# sensor_board_v0_6.net
KiCad netlist of a schematic drawn in EAGLE
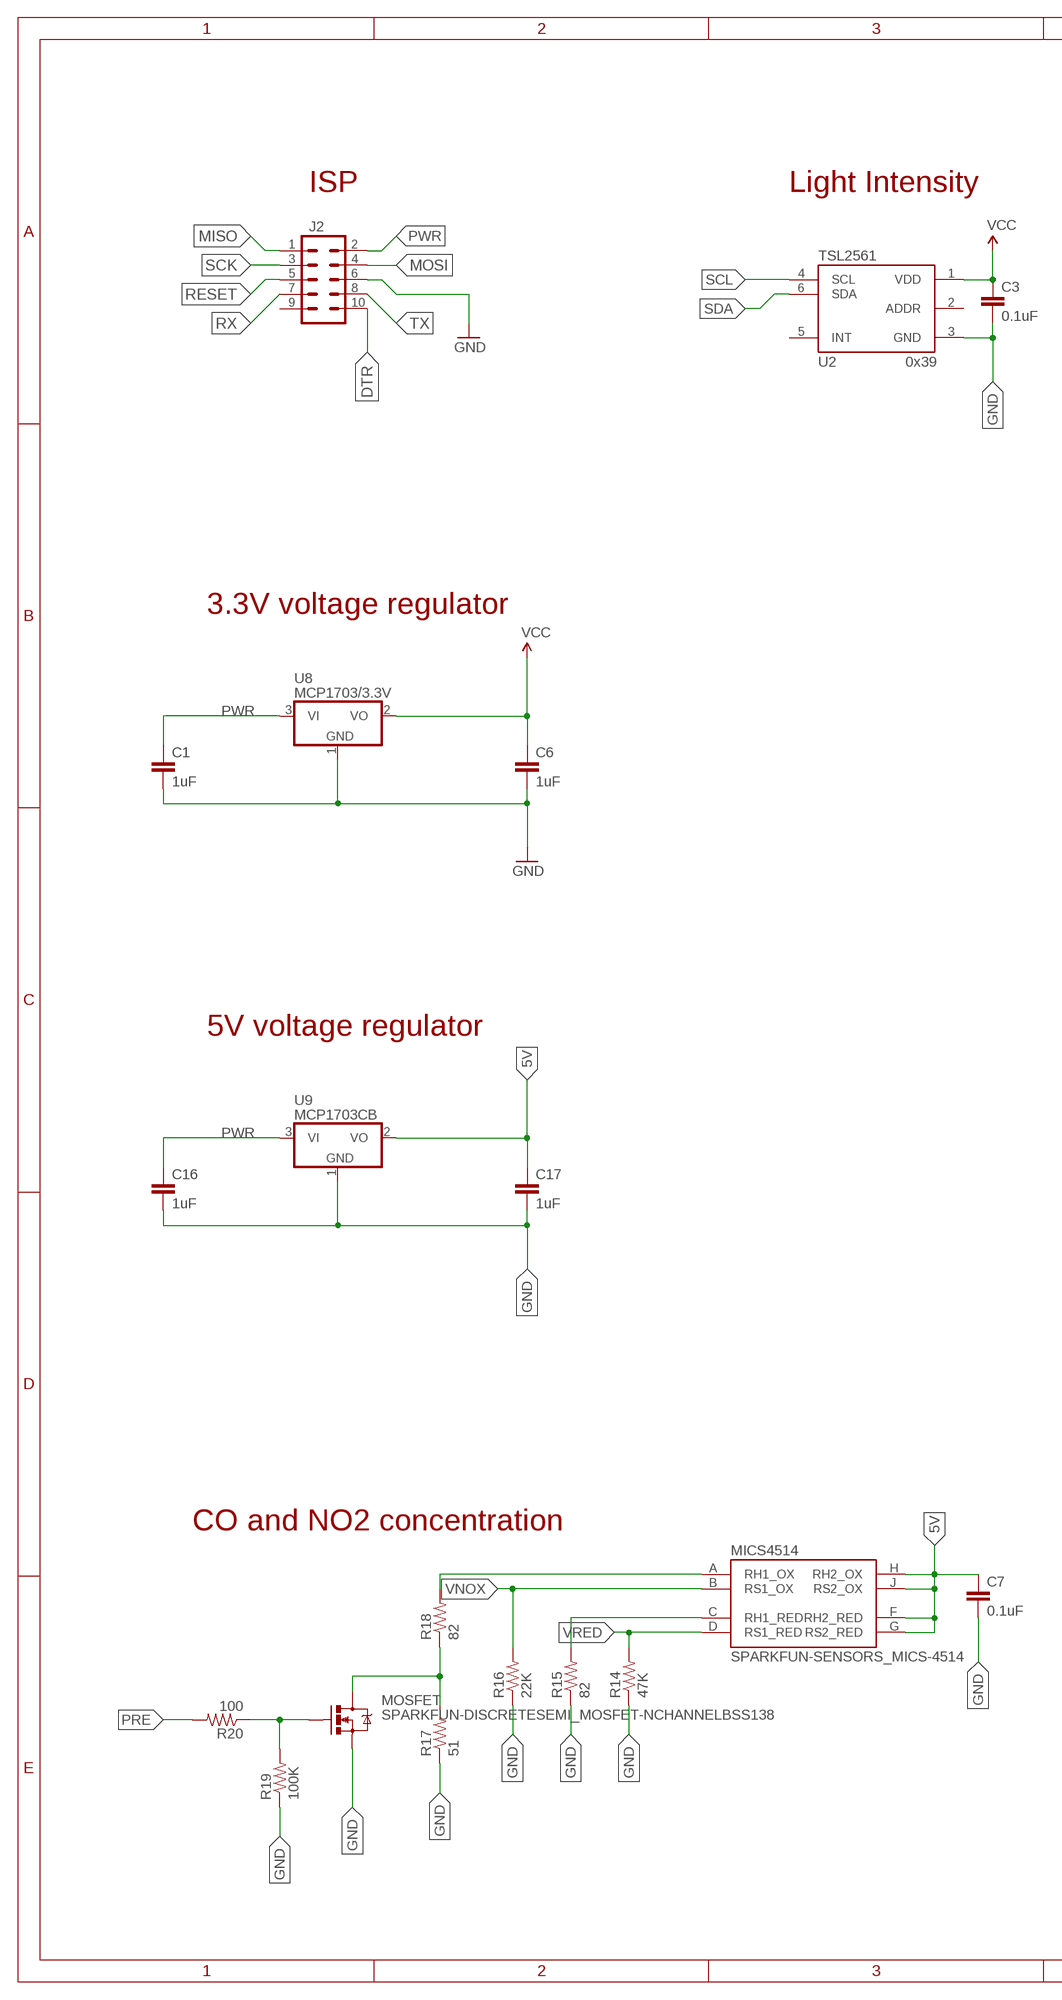
[diagram p0: schematic, sheet 1, part 1 of 2]
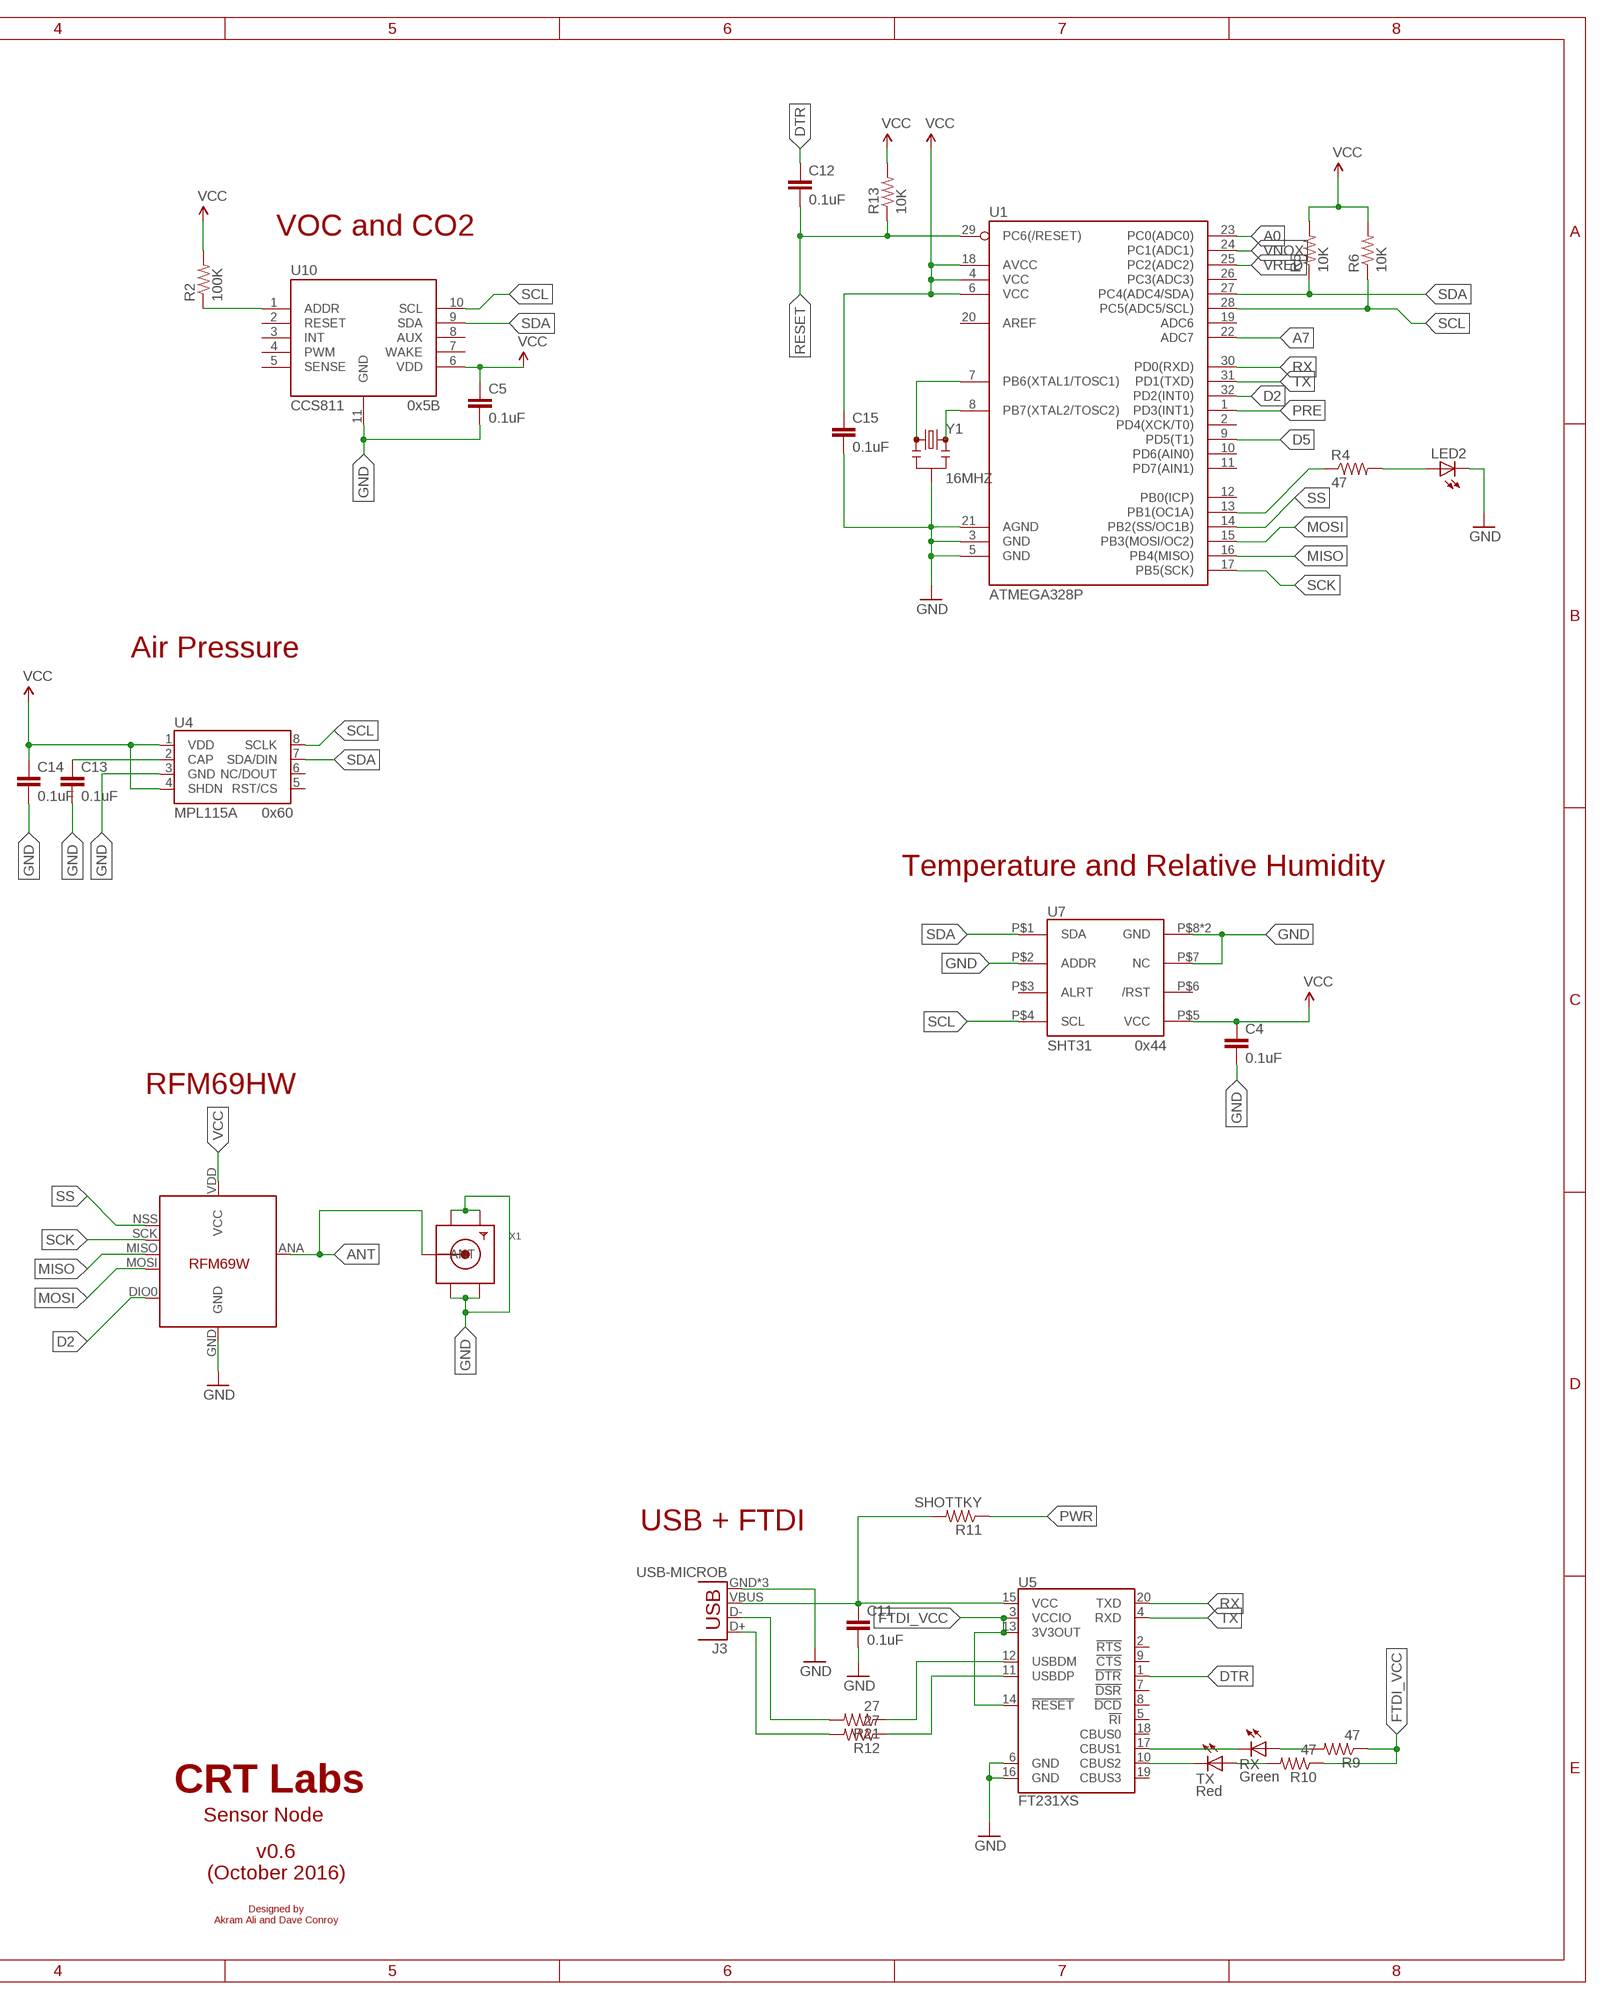
[diagram p1: schematic, sheet 1, part 2 of 2]

(export (version "E")
  (design (tool "Eeschema 10.0.6"))
  (components
    (comp (ref "C1")
      (value "1uF")
      (footprint "eagle-import:0805")
      (libsource (lib "eagle-import") (part "CAP0805"))
    )
    (comp (ref "C3")
      (value "0.1uF")
      (footprint "eagle-import:0805")
      (libsource (lib "eagle-import") (part "SparkFun-Passives_CAP0805"))
    )
    (comp (ref "C4")
      (value "0.1uF")
      (footprint "eagle-import:0805")
      (libsource (lib "eagle-import") (part "SparkFun-Passives_CAP0805"))
    )
    (comp (ref "C5")
      (value "0.1uF")
      (footprint "eagle-import:0805")
      (libsource (lib "eagle-import") (part "SparkFun-Passives_CAP0805"))
    )
    (comp (ref "C6")
      (value "1uF")
      (footprint "eagle-import:0805")
      (libsource (lib "eagle-import") (part "CAP0805"))
    )
    (comp (ref "C7")
      (value "0.1uF")
      (footprint "eagle-import:0805")
      (libsource (lib "eagle-import") (part "SparkFun-Passives_CAP0805"))
    )
    (comp (ref "C11")
      (value "0.1uF")
      (footprint "eagle-import:0805")
      (libsource (lib "eagle-import") (part "CAP0805"))
    )
    (comp (ref "C12")
      (value "0.1uF")
      (footprint "eagle-import:0805")
      (libsource (lib "eagle-import") (part "SparkFun-Passives_CAP0805"))
    )
    (comp (ref "C13")
      (value "0.1uF")
      (footprint "eagle-import:0805")
      (libsource (lib "eagle-import") (part "SparkFun-Passives_CAP0805"))
    )
    (comp (ref "C14")
      (value "0.1uF")
      (footprint "eagle-import:0805")
      (libsource (lib "eagle-import") (part "SparkFun-Passives_CAP0805"))
    )
    (comp (ref "C15")
      (value "0.1uF")
      (footprint "eagle-import:0805")
      (libsource (lib "eagle-import") (part "SparkFun-Passives_CAP0805"))
    )
    (comp (ref "C16")
      (value "1uF")
      (footprint "eagle-import:0805")
      (libsource (lib "eagle-import") (part "CAP0805"))
    )
    (comp (ref "C17")
      (value "1uF")
      (footprint "eagle-import:0805")
      (libsource (lib "eagle-import") (part "CAP0805"))
    )
    (comp (ref "J2")
      (value "M05X2PTH")
      (footprint "eagle-import:AVR_ICSP")
      (libsource (lib "eagle-import") (part "M05X2PTH"))
    )
    (comp (ref "J3")
      (value "USB-MICROB")
      (footprint "eagle-import:USB-MICROB")
      (libsource (lib "eagle-import") (part "USB-MICROB"))
    )
    (comp (ref "LED2")
      (value "LEDCHIPLED_0805")
      (footprint "eagle-import:CHIPLED_0805")
      (libsource (lib "eagle-import") (part "LEDCHIPLED_0805"))
    )
    (comp (ref "MICS4514")
      (value "SPARKFUN-SENSORS_MICS-4514")
      (footprint "eagle-import:SPARKFUN-SENSORS_MICS_10-SMD")
      (libsource (lib "eagle-import") (part "SPARKFUN-SENSORS_MICS-4514"))
    )
    (comp (ref "MOSFET")
      (value "SPARKFUN-DISCRETESEMI_MOSFET-NCHANNELBSS138")
      (footprint "eagle-import:SPARKFUN-DISCRETESEMI_SOT23-3")
      (libsource (lib "eagle-import") (part "SPARKFUN-DISCRETESEMI_MOSFET-NCHANNELBSS138"))
    )
    (comp (ref "R2")
      (value "100K")
      (footprint "eagle-import:0805")
      (libsource (lib "eagle-import") (part "RESISTOR0805-RES"))
    )
    (comp (ref "R4")
      (value "47")
      (footprint "eagle-import:0805")
      (libsource (lib "eagle-import") (part "SparkFun-Resistors_RESISTOR0805-RES"))
    )
    (comp (ref "R5")
      (value "10K")
      (footprint "eagle-import:0805")
      (libsource (lib "eagle-import") (part "SparkFun-Resistors_RESISTOR0805-RES"))
    )
    (comp (ref "R6")
      (value "10K")
      (footprint "eagle-import:0805")
      (libsource (lib "eagle-import") (part "SparkFun-Resistors_RESISTOR0805-RES"))
    )
    (comp (ref "R9")
      (value "47")
      (footprint "eagle-import:0805")
      (libsource (lib "eagle-import") (part "RESISTOR0805-RES"))
    )
    (comp (ref "R10")
      (value "47")
      (footprint "eagle-import:0805")
      (libsource (lib "eagle-import") (part "RESISTOR0805-RES"))
    )
    (comp (ref "R11")
      (value "SHOTTKY")
      (footprint "eagle-import:0805")
      (libsource (lib "eagle-import") (part "RESISTOR0805-RES"))
    )
    (comp (ref "R12")
      (value "27")
      (footprint "eagle-import:0805")
      (libsource (lib "eagle-import") (part "RESISTOR0805-RES"))
    )
    (comp (ref "R13")
      (value "10K")
      (footprint "eagle-import:0805")
      (libsource (lib "eagle-import") (part "RESISTOR0805-RES"))
    )
    (comp (ref "R14")
      (value "47K")
      (footprint "eagle-import:0805")
      (libsource (lib "eagle-import") (part "RESISTOR0805-RES"))
    )
    (comp (ref "R15")
      (value "82")
      (footprint "eagle-import:0805")
      (libsource (lib "eagle-import") (part "RESISTOR0805-RES"))
    )
    (comp (ref "R16")
      (value "22K")
      (footprint "eagle-import:0805")
      (libsource (lib "eagle-import") (part "RESISTOR0805-RES"))
    )
    (comp (ref "R17")
      (value "51")
      (footprint "eagle-import:0805")
      (libsource (lib "eagle-import") (part "RESISTOR0805-RES"))
    )
    (comp (ref "R18")
      (value "82")
      (footprint "eagle-import:0805")
      (libsource (lib "eagle-import") (part "RESISTOR0805-RES"))
    )
    (comp (ref "R19")
      (value "100K")
      (footprint "eagle-import:0805")
      (libsource (lib "eagle-import") (part "RESISTOR0805-RES"))
    )
    (comp (ref "R20")
      (value "100")
      (footprint "eagle-import:0805")
      (libsource (lib "eagle-import") (part "RESISTOR0805-RES"))
    )
    (comp (ref "R21")
      (value "27")
      (footprint "eagle-import:0805")
      (libsource (lib "eagle-import") (part "RESISTOR0805-RES"))
    )
    (comp (ref "RX")
      (value "Green")
      (footprint "eagle-import:CHIPLED_0805")
      (libsource (lib "eagle-import") (part "LEDCHIPLED_0805"))
    )
    (comp (ref "TX")
      (value "Red")
      (footprint "eagle-import:CHIPLED_0805")
      (libsource (lib "eagle-import") (part "LEDCHIPLED_0805"))
    )
    (comp (ref "U1")
      (value "ATMEGA328P")
      (footprint "eagle-import:TQFP32-08")
      (fields (field (name "MPN") "ATMEGA328PB-AU"))
      (libsource (lib "eagle-import") (part "ATMEGA328P_TQFP"))
    )
    (comp (ref "U2")
      (value "TSL2561")
      (footprint "eagle-import:FN-6")
      (fields (field (name "MANF") "AMS-TAOS-USA-Inc.") (field (name "MPN") "TSL2561FN"))
      (libsource (lib "eagle-import") (part "TSL2561FN"))
    )
    (comp (ref "U4")
      (value "MPL115A")
      (footprint "eagle-import:LGA8")
      (libsource (lib "eagle-import") (part "MPL115A"))
    )
    (comp (ref "U5")
      (value "FT231XS")
      (footprint "eagle-import:SSOP20_L")
      (libsource (lib "eagle-import") (part "FT231XS"))
    )
    (comp (ref "U7")
      (value "SHT31")
      (footprint "eagle-import:SHT3X")
      (fields (field (name "MPN") "SHT31-DIS-B"))
      (libsource (lib "eagle-import") (part "SHT31-DIS"))
    )
    (comp (ref "U8")
      (value "MCP1703/3.3V")
      (footprint "eagle-import:SOT23")
      (fields (field (name "MPN") "MCP1703T-2502E/CB"))
      (libsource (lib "eagle-import") (part "MCP1703CB"))
    )
    (comp (ref "U9")
      (value "MCP1703CB")
      (footprint "eagle-import:SOT23")
      (fields (field (name "MPN") "MCP1703T-2502E/CB"))
      (libsource (lib "eagle-import") (part "MCP1703CB"))
    )
    (comp (ref "U10")
      (value "CCS811")
      (footprint "eagle-import:LGA")
      (libsource (lib "eagle-import") (part "CCS811-I2C"))
    )
    (comp (ref "U11")
      (value "RFM69HW")
      (footprint "eagle-import:LOWPOWERLAB_RFM69W-MINPADS")
      (libsource (lib "eagle-import") (part "LOWPOWERLAB_RFM69"))
    )
    (comp (ref "X1")
      (value "SMACONNECTOR_EDGE")
      (footprint "eagle-import:SMA_EDGELAUNCH")
      (libsource (lib "eagle-import") (part "SMACONNECTOR_EDGE"))
    )
    (comp (ref "Y1")
      (value "16MHZ")
      (footprint "eagle-import:RESONATOR-SMD")
      (libsource (lib "eagle-import") (part "RESONATOR16MHZ"))
    )
  )
  (nets
    (net (code "1") (name "5V") (class "Default")
      (node (ref "C17") (pin "1") (pinfunction "1_1") (pintype "passive"))
      (node (ref "C7") (pin "1") (pinfunction "1_1") (pintype "passive"))
      (node (ref "MICS4514") (pin "F") (pinfunction "RH2_RED_F") (pintype "bidirectional"))
      (node (ref "MICS4514") (pin "G") (pinfunction "RS2_RED_G") (pintype "bidirectional"))
      (node (ref "MICS4514") (pin "H") (pinfunction "RH2_OX_H") (pintype "bidirectional"))
      (node (ref "MICS4514") (pin "J") (pinfunction "RS2_OX_J") (pintype "bidirectional"))
      (node (ref "U9") (pin "2") (pinfunction "VO_2") (pintype "passive"))
    )
    (net (code "2") (name "A0") (class "Default")
      (node (ref "U1") (pin "23") (pinfunction "PC0(ADC0)_23") (pintype "bidirectional"))
    )
    (net (code "3") (name "A7") (class "Default")
      (node (ref "U1") (pin "22") (pinfunction "ADC7_22") (pintype "bidirectional"))
    )
    (net (code "4") (name "ANT") (class "Default")
      (node (ref "U11") (pin "ANA") (pinfunction "ANT_ANA") (pintype "passive"))
      (node (ref "X1") (pin "P") (pinfunction "ANT_P") (pintype "bidirectional"))
    )
    (net (code "5") (name "D2") (class "Default")
      (node (ref "U1") (pin "32") (pinfunction "PD2(INT0)_32") (pintype "bidirectional"))
      (node (ref "U11") (pin "DIO0") (pinfunction "DIO0_DIO0") (pintype "open_collector"))
    )
    (net (code "6") (name "D5") (class "Default")
      (node (ref "U1") (pin "9") (pinfunction "PD5(T1)_9") (pintype "bidirectional"))
    )
    (net (code "7") (name "DTR") (class "Default")
      (node (ref "C12") (pin "1") (pinfunction "1_1") (pintype "passive"))
      (node (ref "J2") (pin "10") (pinfunction "10_10") (pintype "passive"))
      (node (ref "U5") (pin "1") (pinfunction "~{DTR}_1") (pintype "bidirectional"))
    )
    (net (code "8") (name "FTDI_VCC") (class "Default")
      (node (ref "R10") (pin "1") (pinfunction "1_1") (pintype "passive"))
      (node (ref "R9") (pin "1") (pinfunction "1_1") (pintype "passive"))
      (node (ref "U5") (pin "13") (pinfunction "3V3OUT_13") (pintype "bidirectional"))
      (node (ref "U5") (pin "14") (pinfunction "~{RESET}_14") (pintype "bidirectional"))
      (node (ref "U5") (pin "3") (pinfunction "VCCIO_3") (pintype "bidirectional"))
    )
    (net (code "9") (name "GND") (class "Default")
      (node (ref "C1") (pin "2") (pinfunction "2_2") (pintype "passive"))
      (node (ref "C11") (pin "2") (pinfunction "2_2") (pintype "passive"))
      (node (ref "C13") (pin "2") (pinfunction "2_2") (pintype "passive"))
      (node (ref "C14") (pin "2") (pinfunction "2_2") (pintype "passive"))
      (node (ref "C15") (pin "2") (pinfunction "2_2") (pintype "passive"))
      (node (ref "C16") (pin "2") (pinfunction "2_2") (pintype "passive"))
      (node (ref "C17") (pin "2") (pinfunction "2_2") (pintype "passive"))
      (node (ref "C3") (pin "2") (pinfunction "2_2") (pintype "passive"))
      (node (ref "C4") (pin "2") (pinfunction "2_2") (pintype "passive"))
      (node (ref "C5") (pin "2") (pinfunction "2_2") (pintype "passive"))
      (node (ref "C6") (pin "2") (pinfunction "2_2") (pintype "passive"))
      (node (ref "C7") (pin "2") (pinfunction "2_2") (pintype "passive"))
      (node (ref "J2") (pin "6") (pinfunction "6_6") (pintype "passive"))
      (node (ref "J3") (pin "GND") (pinfunction "GND_GND") (pintype "bidirectional"))
      (node (ref "J3") (pin "MT1") (pinfunction "GND_MT1") (pintype "bidirectional"))
      (node (ref "J3") (pin "MT2") (pinfunction "GND_MT2") (pintype "bidirectional"))
      (node (ref "LED2") (pin "C") (pinfunction "C_C") (pintype "passive"))
      (node (ref "MOSFET") (pin "2") (pinfunction "S_2") (pintype "passive"))
      (node (ref "R14") (pin "1") (pinfunction "1_1") (pintype "passive"))
      (node (ref "R15") (pin "1") (pinfunction "1_1") (pintype "passive"))
      (node (ref "R16") (pin "1") (pinfunction "1_1") (pintype "passive"))
      (node (ref "R17") (pin "1") (pinfunction "1_1") (pintype "passive"))
      (node (ref "R19") (pin "1") (pinfunction "1_1") (pintype "passive"))
      (node (ref "U1") (pin "21") (pinfunction "AGND_21") (pintype "bidirectional"))
      (node (ref "U1") (pin "3") (pinfunction "GND_3") (pintype "bidirectional"))
      (node (ref "U1") (pin "5") (pinfunction "GND_5") (pintype "bidirectional"))
      (node (ref "U10") (pin "11") (pinfunction "GND_11") (pintype "bidirectional"))
      (node (ref "U11") (pin "GND") (pinfunction "GND_GND") (pintype "power_in"))
      (node (ref "U2") (pin "3") (pinfunction "GND_3") (pintype "power_in"))
      (node (ref "U4") (pin "3") (pinfunction "GND_3") (pintype "bidirectional"))
      (node (ref "U5") (pin "16") (pinfunction "GND_16") (pintype "bidirectional"))
      (node (ref "U5") (pin "6") (pinfunction "GND_6") (pintype "bidirectional"))
      (node (ref "U7") (pin "P$2") (pinfunction "ADDR_P$2") (pintype "bidirectional"))
      (node (ref "U7") (pin "P$7") (pinfunction "NC_P$7") (pintype "bidirectional"))
      (node (ref "U7") (pin "P$8") (pinfunction "GND_P$8") (pintype "bidirectional"))
      (node (ref "U7") (pin "PAD") (pinfunction "GND_PAD") (pintype "bidirectional"))
      (node (ref "U8") (pin "1") (pinfunction "GND_1") (pintype "passive"))
      (node (ref "U9") (pin "1") (pinfunction "GND_1") (pintype "passive"))
      (node (ref "X1") (pin "GND@1") (pinfunction "GND4_GND@1") (pintype "power_in"))
      (node (ref "X1") (pin "GND@2") (pinfunction "GND3_GND@2") (pintype "power_in"))
      (node (ref "X1") (pin "GND@3") (pinfunction "GND2_GND@3") (pintype "power_in"))
      (node (ref "X1") (pin "GND@4") (pinfunction "GND1_GND@4") (pintype "power_in"))
      (node (ref "Y1") (pin "2") (pinfunction "2_2") (pintype "passive"))
    )
    (net (code "10") (name "MISO") (class "Default")
      (node (ref "J2") (pin "1") (pinfunction "1_1") (pintype "passive"))
      (node (ref "U1") (pin "16") (pinfunction "PB4(MISO)_16") (pintype "bidirectional"))
      (node (ref "U11") (pin "MISO") (pinfunction "MISO_MISO") (pintype "input"))
    )
    (net (code "11") (name "MOSI") (class "Default")
      (node (ref "J2") (pin "4") (pinfunction "4_4") (pintype "passive"))
      (node (ref "U1") (pin "15") (pinfunction "PB3(MOSI/OC2)_15") (pintype "bidirectional"))
      (node (ref "U11") (pin "MOSI") (pinfunction "MOSI_MOSI") (pintype "output"))
    )
    (net (code "12") (name "Net-(J3-PadD+)") (class "Default")
      (node (ref "J3") (pin "D+") (pinfunction "D+_D+") (pintype "bidirectional"))
      (node (ref "R12") (pin "2") (pinfunction "2_2") (pintype "passive"))
    )
    (net (code "13") (name "Net-(J3-PadD-)") (class "Default")
      (node (ref "J3") (pin "D-") (pinfunction "D-_D-") (pintype "bidirectional"))
      (node (ref "R21") (pin "2") (pinfunction "2_2") (pintype "passive"))
    )
    (net (code "14") (name "Net-(LED2-PadA)") (class "Default")
      (node (ref "LED2") (pin "A") (pinfunction "A_A") (pintype "passive"))
      (node (ref "R4") (pin "2") (pinfunction "2_2") (pintype "passive"))
    )
    (net (code "15") (name "Net-(MICS4514-RH1_OX)") (class "Default")
      (node (ref "MICS4514") (pin "A") (pinfunction "RH1_OX_A") (pintype "bidirectional"))
      (node (ref "R18") (pin "2") (pinfunction "2_2") (pintype "passive"))
    )
    (net (code "16") (name "Net-(MICS4514-RH1_RED)") (class "Default")
      (node (ref "MICS4514") (pin "C") (pinfunction "RH1_RED_C") (pintype "bidirectional"))
      (node (ref "R15") (pin "2") (pinfunction "2_2") (pintype "passive"))
    )
    (net (code "17") (name "Net-(MOSFET-D)") (class "Default")
      (node (ref "MOSFET") (pin "3") (pinfunction "D_3") (pintype "passive"))
      (node (ref "R17") (pin "2") (pinfunction "2_2") (pintype "passive"))
      (node (ref "R18") (pin "1") (pinfunction "1_1") (pintype "passive"))
    )
    (net (code "18") (name "Net-(MOSFET-G)") (class "Default")
      (node (ref "MOSFET") (pin "1") (pinfunction "G_1") (pintype "passive"))
      (node (ref "R19") (pin "2") (pinfunction "2_2") (pintype "passive"))
      (node (ref "R20") (pin "1") (pinfunction "1_1") (pintype "passive"))
    )
    (net (code "19") (name "Net-(R9-Pad2)") (class "Default")
      (node (ref "R9") (pin "2") (pinfunction "2_2") (pintype "passive"))
      (node (ref "RX") (pin "A") (pinfunction "A_A") (pintype "passive"))
    )
    (net (code "20") (name "Net-(R10-Pad2)") (class "Default")
      (node (ref "R10") (pin "2") (pinfunction "2_2") (pintype "passive"))
      (node (ref "TX") (pin "A") (pinfunction "A_A") (pintype "passive"))
    )
    (net (code "21") (name "Net-(U1-PB1(OC1A))") (class "Default")
      (node (ref "R4") (pin "1") (pinfunction "1_1") (pintype "passive"))
      (node (ref "U1") (pin "13") (pinfunction "PB1(OC1A)_13") (pintype "bidirectional"))
    )
    (net (code "22") (name "Net-(U1-PB6(XTAL1{slash}TOSC1))") (class "Default")
      (node (ref "U1") (pin "7") (pinfunction "PB6(XTAL1/TOSC1)_7") (pintype "bidirectional"))
      (node (ref "Y1") (pin "1") (pinfunction "1_1") (pintype "passive"))
    )
    (net (code "23") (name "Net-(U1-PB7(XTAL2{slash}TOSC2))") (class "Default")
      (node (ref "U1") (pin "8") (pinfunction "PB7(XTAL2/TOSC2)_8") (pintype "bidirectional"))
      (node (ref "Y1") (pin "3") (pinfunction "3_3") (pintype "passive"))
    )
    (net (code "24") (name "Net-(U4-CAP)") (class "Default")
      (node (ref "C13") (pin "1") (pinfunction "1_1") (pintype "passive"))
      (node (ref "U4") (pin "2") (pinfunction "CAP_2") (pintype "bidirectional"))
    )
    (net (code "25") (name "Net-(U5-CBUS1)") (class "Default")
      (node (ref "RX") (pin "C") (pinfunction "C_C") (pintype "passive"))
      (node (ref "U5") (pin "17") (pinfunction "CBUS1_17") (pintype "bidirectional"))
    )
    (net (code "26") (name "Net-(U5-CBUS2)") (class "Default")
      (node (ref "TX") (pin "C") (pinfunction "C_C") (pintype "passive"))
      (node (ref "U5") (pin "10") (pinfunction "CBUS2_10") (pintype "bidirectional"))
    )
    (net (code "27") (name "Net-(U5-USBDM)") (class "Default")
      (node (ref "R21") (pin "1") (pinfunction "1_1") (pintype "passive"))
      (node (ref "U5") (pin "12") (pinfunction "USBDM_12") (pintype "bidirectional"))
    )
    (net (code "28") (name "Net-(U5-USBDP)") (class "Default")
      (node (ref "R12") (pin "1") (pinfunction "1_1") (pintype "passive"))
      (node (ref "U5") (pin "11") (pinfunction "USBDP_11") (pintype "bidirectional"))
    )
    (net (code "29") (name "Net-(U5-VCC)") (class "Default")
      (node (ref "C11") (pin "1") (pinfunction "1_1") (pintype "passive"))
      (node (ref "J3") (pin "VBUS") (pinfunction "VBUS_VBUS") (pintype "bidirectional"))
      (node (ref "R11") (pin "2") (pinfunction "2_2") (pintype "passive"))
      (node (ref "U5") (pin "15") (pinfunction "VCC_15") (pintype "bidirectional"))
    )
    (net (code "30") (name "Net-(U10-ADDR)") (class "Default")
      (node (ref "R2") (pin "1") (pinfunction "1_1") (pintype "passive"))
      (node (ref "U10") (pin "1") (pinfunction "ADDR_1") (pintype "bidirectional"))
    )
    (net (code "31") (name "PRE") (class "Default")
      (node (ref "R20") (pin "2") (pinfunction "2_2") (pintype "passive"))
      (node (ref "U1") (pin "1") (pinfunction "PD3(INT1)_1") (pintype "bidirectional"))
    )
    (net (code "32") (name "PWR") (class "Default")
      (node (ref "C1") (pin "1") (pinfunction "1_1") (pintype "passive"))
      (node (ref "C16") (pin "1") (pinfunction "1_1") (pintype "passive"))
      (node (ref "J2") (pin "2") (pinfunction "2_2") (pintype "passive"))
      (node (ref "R11") (pin "1") (pinfunction "1_1") (pintype "passive"))
      (node (ref "U8") (pin "3") (pinfunction "VI_3") (pintype "input"))
      (node (ref "U9") (pin "3") (pinfunction "VI_3") (pintype "input"))
    )
    (net (code "33") (name "RESET") (class "Default")
      (node (ref "C12") (pin "2") (pinfunction "2_2") (pintype "passive"))
      (node (ref "J2") (pin "5") (pinfunction "5_5") (pintype "passive"))
      (node (ref "R13") (pin "1") (pinfunction "1_1") (pintype "passive"))
      (node (ref "U1") (pin "29") (pinfunction "PC6(/RESET)_29") (pintype "bidirectional"))
    )
    (net (code "34") (name "RX") (class "Default")
      (node (ref "J2") (pin "7") (pinfunction "7_7") (pintype "passive"))
      (node (ref "U1") (pin "30") (pinfunction "PD0(RXD)_30") (pintype "bidirectional"))
      (node (ref "U5") (pin "20") (pinfunction "TXD_20") (pintype "bidirectional"))
    )
    (net (code "35") (name "SCK") (class "Default")
      (node (ref "J2") (pin "3") (pinfunction "3_3") (pintype "passive"))
      (node (ref "U1") (pin "17") (pinfunction "PB5(SCK)_17") (pintype "bidirectional"))
      (node (ref "U11") (pin "SCK") (pinfunction "SCK_SCK") (pintype "input"))
    )
    (net (code "36") (name "SCL") (class "Default")
      (node (ref "R6") (pin "1") (pinfunction "1_1") (pintype "passive"))
      (node (ref "U1") (pin "28") (pinfunction "PC5(ADC5/SCL)_28") (pintype "bidirectional"))
      (node (ref "U10") (pin "10") (pinfunction "SCL_10") (pintype "bidirectional"))
      (node (ref "U2") (pin "4") (pinfunction "SCL_4") (pintype "input"))
      (node (ref "U4") (pin "8") (pinfunction "SCLK_8") (pintype "bidirectional"))
      (node (ref "U7") (pin "P$4") (pinfunction "SCL_P$4") (pintype "bidirectional"))
    )
    (net (code "37") (name "SDA") (class "Default")
      (node (ref "R5") (pin "1") (pinfunction "1_1") (pintype "passive"))
      (node (ref "U1") (pin "27") (pinfunction "PC4(ADC4/SDA)_27") (pintype "bidirectional"))
      (node (ref "U10") (pin "9") (pinfunction "SDA_9") (pintype "bidirectional"))
      (node (ref "U2") (pin "6") (pinfunction "SDA_6") (pintype "bidirectional"))
      (node (ref "U4") (pin "7") (pinfunction "SDA/DIN_7") (pintype "bidirectional"))
      (node (ref "U7") (pin "P$1") (pinfunction "SDA_P$1") (pintype "bidirectional"))
    )
    (net (code "38") (name "SS") (class "Default")
      (node (ref "U1") (pin "14") (pinfunction "PB2(SS/OC1B)_14") (pintype "bidirectional"))
      (node (ref "U11") (pin "NSS") (pinfunction "SEL_NSS") (pintype "input"))
    )
    (net (code "39") (name "TX") (class "Default")
      (node (ref "J2") (pin "8") (pinfunction "8_8") (pintype "passive"))
      (node (ref "U1") (pin "31") (pinfunction "PD1(TXD)_31") (pintype "bidirectional"))
      (node (ref "U5") (pin "4") (pinfunction "RXD_4") (pintype "bidirectional"))
    )
    (net (code "40") (name "VCC") (class "Default")
      (node (ref "C14") (pin "1") (pinfunction "1_1") (pintype "passive"))
      (node (ref "C15") (pin "1") (pinfunction "1_1") (pintype "passive"))
      (node (ref "C3") (pin "1") (pinfunction "1_1") (pintype "passive"))
      (node (ref "C4") (pin "1") (pinfunction "1_1") (pintype "passive"))
      (node (ref "C5") (pin "1") (pinfunction "1_1") (pintype "passive"))
      (node (ref "C6") (pin "1") (pinfunction "1_1") (pintype "passive"))
      (node (ref "R13") (pin "2") (pinfunction "2_2") (pintype "passive"))
      (node (ref "R2") (pin "2") (pinfunction "2_2") (pintype "passive"))
      (node (ref "R5") (pin "2") (pinfunction "2_2") (pintype "passive"))
      (node (ref "R6") (pin "2") (pinfunction "2_2") (pintype "passive"))
      (node (ref "U1") (pin "18") (pinfunction "AVCC_18") (pintype "bidirectional"))
      (node (ref "U1") (pin "4") (pinfunction "VCC_4") (pintype "bidirectional"))
      (node (ref "U1") (pin "6") (pinfunction "VCC_6") (pintype "bidirectional"))
      (node (ref "U10") (pin "6") (pinfunction "VDD_6") (pintype "bidirectional"))
      (node (ref "U11") (pin "VDD") (pinfunction "VCC_VDD") (pintype "power_in"))
      (node (ref "U2") (pin "1") (pinfunction "VDD_1") (pintype "power_in"))
      (node (ref "U4") (pin "1") (pinfunction "VDD_1") (pintype "bidirectional"))
      (node (ref "U4") (pin "4") (pinfunction "SHDN_4") (pintype "bidirectional"))
      (node (ref "U7") (pin "P$5") (pinfunction "VCC_P$5") (pintype "bidirectional"))
      (node (ref "U8") (pin "2") (pinfunction "VO_2") (pintype "passive"))
    )
    (net (code "41") (name "VNOX") (class "Default")
      (node (ref "MICS4514") (pin "B") (pinfunction "RS1_OX_B") (pintype "bidirectional"))
      (node (ref "R16") (pin "2") (pinfunction "2_2") (pintype "passive"))
      (node (ref "U1") (pin "24") (pinfunction "PC1(ADC1)_24") (pintype "bidirectional"))
    )
    (net (code "42") (name "VRED") (class "Default")
      (node (ref "MICS4514") (pin "D") (pinfunction "RS1_RED_D") (pintype "bidirectional"))
      (node (ref "R14") (pin "2") (pinfunction "2_2") (pintype "passive"))
      (node (ref "U1") (pin "25") (pinfunction "PC2(ADC2)_25") (pintype "bidirectional"))
    )
    (net (code "43") (name "unconnected-(J2-Pad9)") (class "Default")
      (node (ref "J2") (pin "9") (pinfunction "9_9") (pintype "passive"))
    )
    (net (code "44") (name "unconnected-(U1-ADC6-Pad19)") (class "Default")
      (node (ref "U1") (pin "19") (pinfunction "ADC6_19") (pintype "bidirectional"))
    )
    (net (code "45") (name "unconnected-(U1-AREF-Pad20)") (class "Default")
      (node (ref "U1") (pin "20") (pinfunction "AREF_20") (pintype "bidirectional"))
    )
    (net (code "46") (name "unconnected-(U1-PB0(ICP)-Pad12)") (class "Default")
      (node (ref "U1") (pin "12") (pinfunction "PB0(ICP)_12") (pintype "bidirectional"))
    )
    (net (code "47") (name "unconnected-(U1-PC3(ADC3)-Pad26)") (class "Default")
      (node (ref "U1") (pin "26") (pinfunction "PC3(ADC3)_26") (pintype "bidirectional"))
    )
    (net (code "48") (name "unconnected-(U1-PD4(XCK{slash}T0)-Pad2)") (class "Default")
      (node (ref "U1") (pin "2") (pinfunction "PD4(XCK/T0)_2") (pintype "bidirectional"))
    )
    (net (code "49") (name "unconnected-(U1-PD6(AIN0)-Pad10)") (class "Default")
      (node (ref "U1") (pin "10") (pinfunction "PD6(AIN0)_10") (pintype "bidirectional"))
    )
    (net (code "50") (name "unconnected-(U1-PD7(AIN1)-Pad11)") (class "Default")
      (node (ref "U1") (pin "11") (pinfunction "PD7(AIN1)_11") (pintype "bidirectional"))
    )
    (net (code "51") (name "unconnected-(U2-ADDR-Pad2)") (class "Default")
      (node (ref "U2") (pin "2") (pinfunction "ADDR_2") (pintype "input"))
    )
    (net (code "52") (name "unconnected-(U2-INT-Pad5)") (class "Default")
      (node (ref "U2") (pin "5") (pinfunction "INT_5") (pintype "output"))
    )
    (net (code "53") (name "unconnected-(U4-NC{slash}DOUT-Pad6)") (class "Default")
      (node (ref "U4") (pin "6") (pinfunction "NC/DOUT_6") (pintype "bidirectional"))
    )
    (net (code "54") (name "unconnected-(U4-RST{slash}CS-Pad5)") (class "Default")
      (node (ref "U4") (pin "5") (pinfunction "RST/CS_5") (pintype "bidirectional"))
    )
    (net (code "55") (name "unconnected-(U5-CBUS0-Pad18)") (class "Default")
      (node (ref "U5") (pin "18") (pinfunction "CBUS0_18") (pintype "bidirectional"))
    )
    (net (code "56") (name "unconnected-(U5-CBUS3-Pad19)") (class "Default")
      (node (ref "U5") (pin "19") (pinfunction "CBUS3_19") (pintype "bidirectional"))
    )
    (net (code "57") (name "unconnected-(U5-~{CTS}-Pad9)") (class "Default")
      (node (ref "U5") (pin "9") (pinfunction "~{CTS}_9") (pintype "bidirectional"))
    )
    (net (code "58") (name "unconnected-(U5-~{DCD}-Pad8)") (class "Default")
      (node (ref "U5") (pin "8") (pinfunction "~{DCD}_8") (pintype "bidirectional"))
    )
    (net (code "59") (name "unconnected-(U5-~{DSR}-Pad7)") (class "Default")
      (node (ref "U5") (pin "7") (pinfunction "~{DSR}_7") (pintype "bidirectional"))
    )
    (net (code "60") (name "unconnected-(U5-~{RI}-Pad5)") (class "Default")
      (node (ref "U5") (pin "5") (pinfunction "~{RI}_5") (pintype "bidirectional"))
    )
    (net (code "61") (name "unconnected-(U5-~{RTS}-Pad2)") (class "Default")
      (node (ref "U5") (pin "2") (pinfunction "~{RTS}_2") (pintype "bidirectional"))
    )
    (net (code "62") (name "unconnected-(U7-ALRT-PadP$3)") (class "Default")
      (node (ref "U7") (pin "P$3") (pinfunction "ALRT_P$3") (pintype "bidirectional"))
    )
    (net (code "63") (name "unconnected-(U7-{slash}RST-PadP$6)") (class "Default")
      (node (ref "U7") (pin "P$6") (pinfunction "/RST_P$6") (pintype "bidirectional"))
    )
    (net (code "64") (name "unconnected-(U10-AUX-Pad8)") (class "Default")
      (node (ref "U10") (pin "8") (pinfunction "AUX_8") (pintype "bidirectional"))
    )
    (net (code "65") (name "unconnected-(U10-INT-Pad3)") (class "Default")
      (node (ref "U10") (pin "3") (pinfunction "INT_3") (pintype "bidirectional"))
    )
    (net (code "66") (name "unconnected-(U10-PWM-Pad4)") (class "Default")
      (node (ref "U10") (pin "4") (pinfunction "PWM_4") (pintype "bidirectional"))
    )
    (net (code "67") (name "unconnected-(U10-RESET-Pad2)") (class "Default")
      (node (ref "U10") (pin "2") (pinfunction "RESET_2") (pintype "bidirectional"))
    )
    (net (code "68") (name "unconnected-(U10-SENSE-Pad5)") (class "Default")
      (node (ref "U10") (pin "5") (pinfunction "SENSE_5") (pintype "bidirectional"))
    )
    (net (code "69") (name "unconnected-(U10-WAKE-Pad7)") (class "Default")
      (node (ref "U10") (pin "7") (pinfunction "WAKE_7") (pintype "bidirectional"))
    )
  )
)
